# Maple_Mini_jr1.net
KiCad netlist of a schematic drawn in EAGLE
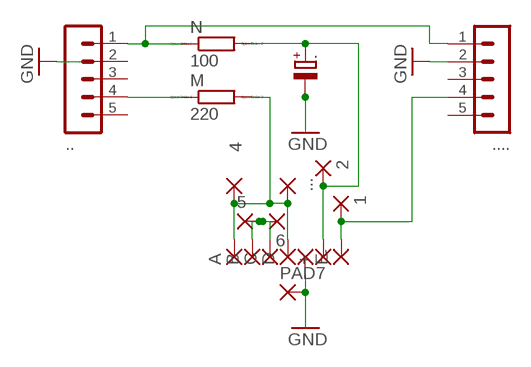
[diagram p0: schematic, sheet 1]

(export (version "E")
  (design (tool "Eeschema 10.0.6"))
  (components
    (comp (ref "+")
      (value "SMD2")
      (footprint "eagle-import:SMD1,27-2,54")
      (libsource (lib "eagle-import") (part "SMD2"))
    )
    (comp (ref "-")
      (value "SMD2")
      (footprint "eagle-import:SMD1,27-2,54")
      (libsource (lib "eagle-import") (part "SMD2"))
    )
    (comp (ref ".")
      (value "CPOL-EUE1.8-4")
      (footprint "eagle-import:E1,8-4")
      (libsource (lib "eagle-import") (part "CPOL-EUE1.8-4"))
    )
    (comp (ref "..")
      (value "MA05-1")
      (footprint "eagle-import:MA05-1")
      (libsource (lib "eagle-import") (part "MA05-1"))
    )
    (comp (ref "...")
      (value "SMD2")
      (footprint "eagle-import:SMD1,27-2,54")
      (libsource (lib "eagle-import") (part "SMD2"))
    )
    (comp (ref "....")
      (value "MA05-1")
      (footprint "eagle-import:MA05-1")
      (libsource (lib "eagle-import") (part "MA05-1"))
    )
    (comp (ref "1")
      (value "SMD2")
      (footprint "eagle-import:SMD1,27-2,54")
      (libsource (lib "eagle-import") (part "SMD2"))
    )
    (comp (ref "2")
      (value "SMD2")
      (footprint "eagle-import:SMD1,27-2,54")
      (libsource (lib "eagle-import") (part "SMD2"))
    )
    (comp (ref "4")
      (value "SMD2")
      (footprint "eagle-import:SMD1,27-2,54")
      (libsource (lib "eagle-import") (part "SMD2"))
    )
    (comp (ref "5")
      (value "SMD2")
      (footprint "eagle-import:SMD1,27-2,54")
      (libsource (lib "eagle-import") (part "SMD2"))
    )
    (comp (ref "6")
      (value "SMD2")
      (footprint "eagle-import:SMD1,27-2,54")
      (libsource (lib "eagle-import") (part "SMD2"))
    )
    (comp (ref "A")
      (value "SMD2")
      (footprint "eagle-import:SMD1,27-2,54")
      (libsource (lib "eagle-import") (part "SMD2"))
    )
    (comp (ref "B")
      (value "SMD2")
      (footprint "eagle-import:SMD1,27-2,54")
      (libsource (lib "eagle-import") (part "SMD2"))
    )
    (comp (ref "C")
      (value "SMD2")
      (footprint "eagle-import:SMD1,27-2,54")
      (libsource (lib "eagle-import") (part "SMD2"))
    )
    (comp (ref "D")
      (value "SMD2")
      (footprint "eagle-import:SMD1,27-2,54")
      (libsource (lib "eagle-import") (part "SMD2"))
    )
    (comp (ref "E")
      (value "SMD2")
      (footprint "eagle-import:SMD1,27-2,54")
      (libsource (lib "eagle-import") (part "SMD2"))
    )
    (comp (ref "M")
      (value "220")
      (footprint "eagle-import:0204_7")
      (libsource (lib "eagle-import") (part "R0204/7"))
    )
    (comp (ref "N")
      (value "100")
      (footprint "eagle-import:0204_7")
      (libsource (lib "eagle-import") (part "R0204/7"))
    )
    (comp (ref "PAD7")
      (value "SMD2")
      (footprint "eagle-import:SMD1,27-2,54")
      (libsource (lib "eagle-import") (part "SMD2"))
    )
  )
  (nets
    (net (code "1") (name "GND") (class "Default")
      (node (ref "-") (pin "1") (pinfunction "P_1") (pintype "passive"))
      (node (ref ".") (pin "-") (pinfunction "-_-") (pintype "passive"))
      (node (ref "....") (pin "2") (pinfunction "2_2") (pintype "passive"))
      (node (ref "PAD7") (pin "1") (pinfunction "P_1") (pintype "passive"))
    )
    (net (code "2") (name "Net-(+-P)") (class "Default")
      (node (ref "+") (pin "1") (pinfunction "P_1") (pintype "passive"))
      (node (ref ".") (pin "+") (pinfunction "+_+") (pintype "passive"))
      (node (ref "2") (pin "1") (pinfunction "P_1") (pintype "passive"))
      (node (ref "N") (pin "2") (pinfunction "2_2") (pintype "passive"))
    )
    (net (code "3") (name "Net-(..-Pad1)") (class "Default")
      (node (ref "..") (pin "1") (pinfunction "1_1") (pintype "passive"))
      (node (ref "....") (pin "1") (pinfunction "1_1") (pintype "passive"))
      (node (ref "N") (pin "1") (pinfunction "1_1") (pintype "passive"))
    )
    (net (code "4") (name "Net-(..-Pad4)") (class "Default")
      (node (ref "..") (pin "4") (pinfunction "4_4") (pintype "passive"))
      (node (ref "M") (pin "1") (pinfunction "1_1") (pintype "passive"))
    )
    (net (code "5") (name "Net-(...-P)") (class "Default")
      (node (ref "...") (pin "1") (pinfunction "P_1") (pintype "passive"))
      (node (ref "4") (pin "1") (pinfunction "P_1") (pintype "passive"))
      (node (ref "A") (pin "1") (pinfunction "P_1") (pintype "passive"))
      (node (ref "D") (pin "1") (pinfunction "P_1") (pintype "passive"))
      (node (ref "M") (pin "2") (pinfunction "2_2") (pintype "passive"))
    )
    (net (code "6") (name "Net-(1-P)") (class "Default")
      (node (ref "....") (pin "4") (pinfunction "4_4") (pintype "passive"))
      (node (ref "1") (pin "1") (pinfunction "P_1") (pintype "passive"))
      (node (ref "E") (pin "1") (pinfunction "P_1") (pintype "passive"))
    )
    (net (code "7") (name "Net-(5-P)") (class "Default")
      (node (ref "5") (pin "1") (pinfunction "P_1") (pintype "passive"))
      (node (ref "6") (pin "1") (pinfunction "P_1") (pintype "passive"))
      (node (ref "B") (pin "1") (pinfunction "P_1") (pintype "passive"))
      (node (ref "C") (pin "1") (pinfunction "P_1") (pintype "passive"))
    )
    (net (code "8") (name "unconnected-(..-Pad2)") (class "Default")
      (node (ref "..") (pin "2") (pinfunction "2_2") (pintype "passive"))
    )
    (net (code "9") (name "unconnected-(..-Pad3)") (class "Default")
      (node (ref "..") (pin "3") (pinfunction "3_3") (pintype "passive"))
    )
    (net (code "10") (name "unconnected-(..-Pad5)") (class "Default")
      (node (ref "..") (pin "5") (pinfunction "5_5") (pintype "passive"))
    )
    (net (code "11") (name "unconnected-(....-Pad3)") (class "Default")
      (node (ref "....") (pin "3") (pinfunction "3_3") (pintype "passive"))
    )
    (net (code "12") (name "unconnected-(....-Pad5)") (class "Default")
      (node (ref "....") (pin "5") (pinfunction "5_5") (pintype "passive"))
    )
  )
)
